# despertador.net
KiCad netlist of a schematic drawn in EAGLE
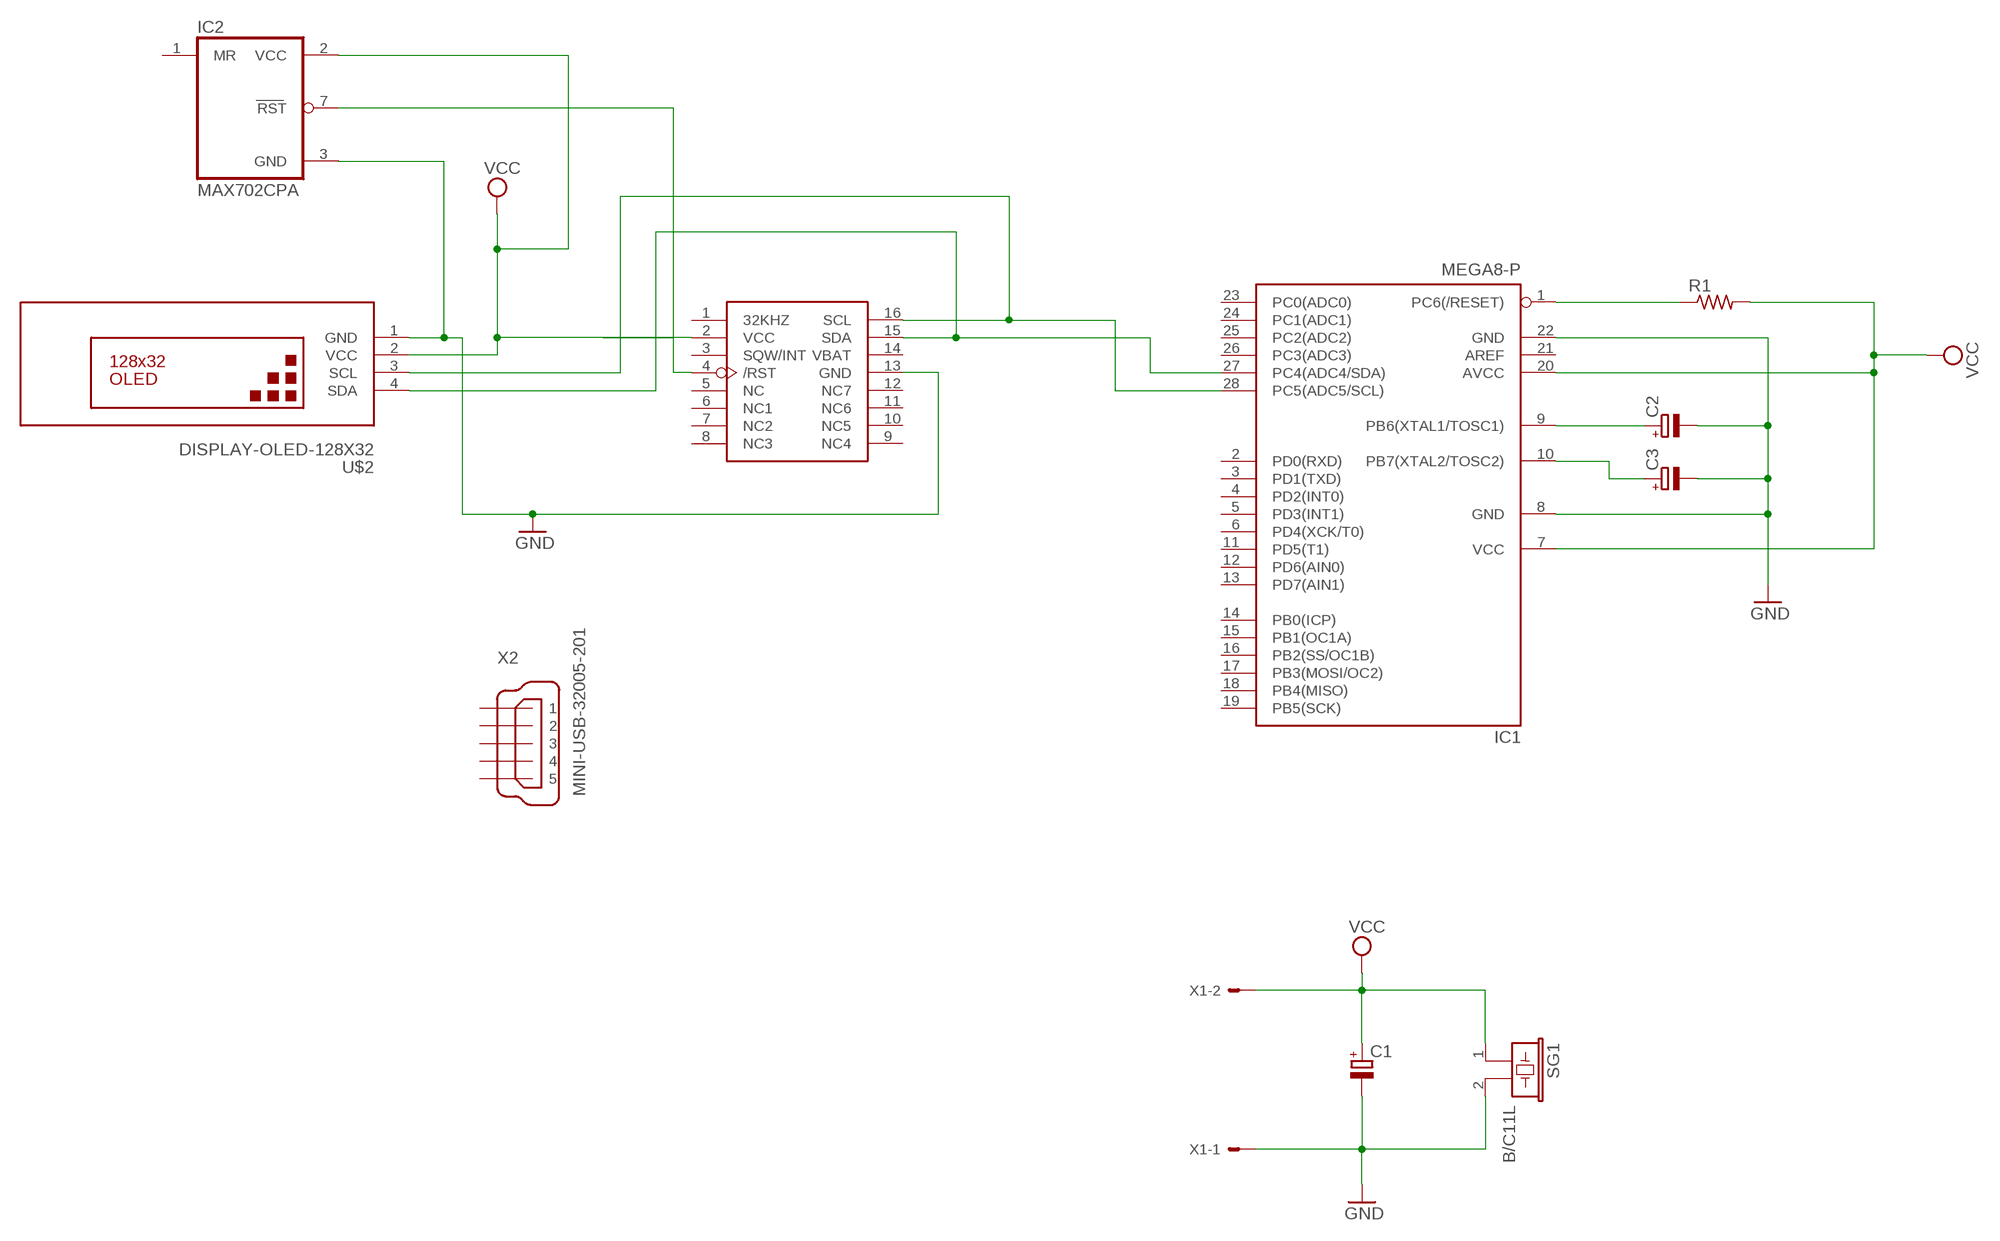
[diagram p0: schematic, sheet 1]

(export (version "E")
  (design (tool "Eeschema 10.0.6"))
  (components
    (comp (ref "C1")
      (value "CPOL-EUE2.5-6")
      (footprint "eagle-import:E2,5-6")
      (libsource (lib "eagle-import") (part "CPOL-EUE2.5-6"))
    )
    (comp (ref "C2")
      (value "CPOL-EUE2.5-6")
      (footprint "eagle-import:E2,5-6")
      (libsource (lib "eagle-import") (part "CPOL-EUE2.5-6"))
    )
    (comp (ref "C3")
      (value "CPOL-EUE2.5-6")
      (footprint "eagle-import:E2,5-6")
      (libsource (lib "eagle-import") (part "CPOL-EUE2.5-6"))
    )
    (comp (ref "IC1")
      (value "MEGA8-P")
      (footprint "eagle-import:DIL28-3")
      (libsource (lib "eagle-import") (part "MEGA8-P"))
    )
    (comp (ref "IC2")
      (value "MAX702CPA")
      (footprint "eagle-import:DIL08")
      (fields (field (name "MF") "MAXIM") (field (name "MPN") "MAX702CPA+"))
      (libsource (lib "eagle-import") (part "MAX702CPA"))
    )
    (comp (ref "R1")
      (value "R-US_0207/10")
      (footprint "eagle-import:0207_10")
      (libsource (lib "eagle-import") (part "R-US_0207/10"))
    )
    (comp (ref "SG1")
      (value "B/C11L")
      (footprint "eagle-import:B_C11L")
      (libsource (lib "eagle-import") (part "B/C11L"))
    )
    (comp (ref "U$2")
      (value "DISPLAY-OLED-128X32")
      (footprint "eagle-import:DISPLAY-OLED-128X32")
      (libsource (lib "eagle-import") (part "DISPLAY-OLED-128X32"))
    )
    (comp (ref "U$3")
      (value "DS3231")
      (footprint "eagle-import:PDIP")
      (libsource (lib "eagle-import") (part "DS3231"))
    )
    (comp (ref "X1")
      (value "KK-156-2")
      (footprint "eagle-import:KK-156-2")
      (fields (field (name "MF") "MOLEX"))
      (libsource (lib "eagle-import") (part "KK-156-2"))
    )
    (comp (ref "X2")
      (value "MINI-USB-32005-201")
      (footprint "eagle-import:32005-201")
      (libsource (lib "eagle-import") (part "MINI-USB-32005-201"))
    )
  )
  (nets
    (net (code "1") (name "GND") (class "Default")
      (node (ref "C1") (pin "-") (pinfunction "-_-") (pintype "passive"))
      (node (ref "C2") (pin "-") (pinfunction "-_-") (pintype "passive"))
      (node (ref "C3") (pin "-") (pinfunction "-_-") (pintype "passive"))
      (node (ref "IC1") (pin "22") (pinfunction "GND_22") (pintype "power_in"))
      (node (ref "IC1") (pin "8") (pinfunction "GND_8") (pintype "power_in"))
      (node (ref "IC2") (pin "3") (pinfunction "GND_3") (pintype "power_in"))
      (node (ref "SG1") (pin "2") (pinfunction "2_2") (pintype "passive"))
      (node (ref "U$2") (pin "1") (pinfunction "GND_1") (pintype "power_in"))
      (node (ref "U$3") (pin "13") (pinfunction "GND_13") (pintype "power_in"))
      (node (ref "X1") (pin "1") (pinfunction "S_1") (pintype "passive"))
    )
    (net (code "2") (name "Net-(IC1-PB6(XTAL1{slash}TOSC1))") (class "Default")
      (node (ref "C2") (pin "+") (pinfunction "+_+") (pintype "passive"))
      (node (ref "IC1") (pin "9") (pinfunction "PB6(XTAL1/TOSC1)_9") (pintype "bidirectional"))
    )
    (net (code "3") (name "Net-(IC1-PB7(XTAL2{slash}TOSC2))") (class "Default")
      (node (ref "C3") (pin "+") (pinfunction "+_+") (pintype "passive"))
      (node (ref "IC1") (pin "10") (pinfunction "PB7(XTAL2/TOSC2)_10") (pintype "bidirectional"))
    )
    (net (code "4") (name "Net-(IC1-PC4(ADC4{slash}SDA))") (class "Default")
      (node (ref "IC1") (pin "27") (pinfunction "PC4(ADC4/SDA)_27") (pintype "bidirectional"))
      (node (ref "U$2") (pin "4") (pinfunction "SDA_4") (pintype "bidirectional"))
      (node (ref "U$3") (pin "15") (pinfunction "SDA_15") (pintype "bidirectional"))
    )
    (net (code "5") (name "Net-(IC1-PC5(ADC5{slash}SCL))") (class "Default")
      (node (ref "IC1") (pin "28") (pinfunction "PC5(ADC5/SCL)_28") (pintype "bidirectional"))
      (node (ref "U$2") (pin "3") (pinfunction "SCL_3") (pintype "bidirectional"))
      (node (ref "U$3") (pin "16") (pinfunction "SCL_16") (pintype "bidirectional"))
    )
    (net (code "6") (name "Net-(IC1-PC6({slash}RESET))") (class "Default")
      (node (ref "IC1") (pin "1") (pinfunction "PC6(/RESET)_1") (pintype "bidirectional"))
      (node (ref "R1") (pin "1") (pinfunction "1_1") (pintype "passive"))
    )
    (net (code "7") (name "Net-(IC2-RST)") (class "Default")
      (node (ref "IC2") (pin "7") (pinfunction "RST_7") (pintype "output"))
      (node (ref "U$3") (pin "4") (pinfunction "/RST_4") (pintype "bidirectional"))
    )
    (net (code "8") (name "VCC") (class "Default")
      (node (ref "C1") (pin "+") (pinfunction "+_+") (pintype "passive"))
      (node (ref "IC1") (pin "20") (pinfunction "AVCC_20") (pintype "power_in"))
      (node (ref "IC1") (pin "7") (pinfunction "VCC_7") (pintype "power_in"))
      (node (ref "IC2") (pin "2") (pinfunction "VCC_2") (pintype "power_in"))
      (node (ref "R1") (pin "2") (pinfunction "2_2") (pintype "passive"))
      (node (ref "SG1") (pin "1") (pinfunction "1_1") (pintype "passive"))
      (node (ref "U$2") (pin "2") (pinfunction "VCC_2") (pintype "power_in"))
      (node (ref "U$3") (pin "2") (pinfunction "VCC_2") (pintype "power_in"))
      (node (ref "X1") (pin "2") (pinfunction "S_2") (pintype "passive"))
    )
    (net (code "9") (name "unconnected-(IC1-AREF-Pad21)") (class "Default")
      (node (ref "IC1") (pin "21") (pinfunction "AREF_21") (pintype "passive"))
    )
    (net (code "10") (name "unconnected-(IC1-PB0(ICP)-Pad14)") (class "Default")
      (node (ref "IC1") (pin "14") (pinfunction "PB0(ICP)_14") (pintype "bidirectional"))
    )
    (net (code "11") (name "unconnected-(IC1-PB1(OC1A)-Pad15)") (class "Default")
      (node (ref "IC1") (pin "15") (pinfunction "PB1(OC1A)_15") (pintype "bidirectional"))
    )
    (net (code "12") (name "unconnected-(IC1-PB2(SS{slash}OC1B)-Pad16)") (class "Default")
      (node (ref "IC1") (pin "16") (pinfunction "PB2(SS/OC1B)_16") (pintype "bidirectional"))
    )
    (net (code "13") (name "unconnected-(IC1-PB3(MOSI{slash}OC2)-Pad17)") (class "Default")
      (node (ref "IC1") (pin "17") (pinfunction "PB3(MOSI/OC2)_17") (pintype "bidirectional"))
    )
    (net (code "14") (name "unconnected-(IC1-PB4(MISO)-Pad18)") (class "Default")
      (node (ref "IC1") (pin "18") (pinfunction "PB4(MISO)_18") (pintype "bidirectional"))
    )
    (net (code "15") (name "unconnected-(IC1-PB5(SCK)-Pad19)") (class "Default")
      (node (ref "IC1") (pin "19") (pinfunction "PB5(SCK)_19") (pintype "bidirectional"))
    )
    (net (code "16") (name "unconnected-(IC1-PC0(ADC0)-Pad23)") (class "Default")
      (node (ref "IC1") (pin "23") (pinfunction "PC0(ADC0)_23") (pintype "bidirectional"))
    )
    (net (code "17") (name "unconnected-(IC1-PC1(ADC1)-Pad24)") (class "Default")
      (node (ref "IC1") (pin "24") (pinfunction "PC1(ADC1)_24") (pintype "bidirectional"))
    )
    (net (code "18") (name "unconnected-(IC1-PC2(ADC2)-Pad25)") (class "Default")
      (node (ref "IC1") (pin "25") (pinfunction "PC2(ADC2)_25") (pintype "bidirectional"))
    )
    (net (code "19") (name "unconnected-(IC1-PC3(ADC3)-Pad26)") (class "Default")
      (node (ref "IC1") (pin "26") (pinfunction "PC3(ADC3)_26") (pintype "bidirectional"))
    )
    (net (code "20") (name "unconnected-(IC1-PD0(RXD)-Pad2)") (class "Default")
      (node (ref "IC1") (pin "2") (pinfunction "PD0(RXD)_2") (pintype "bidirectional"))
    )
    (net (code "21") (name "unconnected-(IC1-PD1(TXD)-Pad3)") (class "Default")
      (node (ref "IC1") (pin "3") (pinfunction "PD1(TXD)_3") (pintype "bidirectional"))
    )
    (net (code "22") (name "unconnected-(IC1-PD2(INT0)-Pad4)") (class "Default")
      (node (ref "IC1") (pin "4") (pinfunction "PD2(INT0)_4") (pintype "bidirectional"))
    )
    (net (code "23") (name "unconnected-(IC1-PD3(INT1)-Pad5)") (class "Default")
      (node (ref "IC1") (pin "5") (pinfunction "PD3(INT1)_5") (pintype "bidirectional"))
    )
    (net (code "24") (name "unconnected-(IC1-PD4(XCK{slash}T0)-Pad6)") (class "Default")
      (node (ref "IC1") (pin "6") (pinfunction "PD4(XCK/T0)_6") (pintype "bidirectional"))
    )
    (net (code "25") (name "unconnected-(IC1-PD5(T1)-Pad11)") (class "Default")
      (node (ref "IC1") (pin "11") (pinfunction "PD5(T1)_11") (pintype "bidirectional"))
    )
    (net (code "26") (name "unconnected-(IC1-PD6(AIN0)-Pad12)") (class "Default")
      (node (ref "IC1") (pin "12") (pinfunction "PD6(AIN0)_12") (pintype "bidirectional"))
    )
    (net (code "27") (name "unconnected-(IC1-PD7(AIN1)-Pad13)") (class "Default")
      (node (ref "IC1") (pin "13") (pinfunction "PD7(AIN1)_13") (pintype "bidirectional"))
    )
    (net (code "28") (name "unconnected-(IC2-MR-Pad1)") (class "Default")
      (node (ref "IC2") (pin "1") (pinfunction "MR_1") (pintype "input"))
    )
    (net (code "29") (name "unconnected-(U$3-32KHZ-Pad1)") (class "Default")
      (node (ref "U$3") (pin "1") (pinfunction "32KHZ_1") (pintype "bidirectional"))
    )
    (net (code "30") (name "unconnected-(U$3-NC-Pad5)") (class "Default")
      (node (ref "U$3") (pin "5") (pinfunction "NC_5") (pintype "bidirectional"))
    )
    (net (code "31") (name "unconnected-(U$3-NC1-Pad6)") (class "Default")
      (node (ref "U$3") (pin "6") (pinfunction "NC1_6") (pintype "bidirectional"))
    )
    (net (code "32") (name "unconnected-(U$3-NC2-Pad7)") (class "Default")
      (node (ref "U$3") (pin "7") (pinfunction "NC2_7") (pintype "bidirectional"))
    )
    (net (code "33") (name "unconnected-(U$3-NC3-Pad8)") (class "Default")
      (node (ref "U$3") (pin "8") (pinfunction "NC3_8") (pintype "bidirectional"))
    )
    (net (code "34") (name "unconnected-(U$3-NC4-Pad9)") (class "Default")
      (node (ref "U$3") (pin "9") (pinfunction "NC4_9") (pintype "bidirectional"))
    )
    (net (code "35") (name "unconnected-(U$3-NC5-Pad10)") (class "Default")
      (node (ref "U$3") (pin "10") (pinfunction "NC5_10") (pintype "bidirectional"))
    )
    (net (code "36") (name "unconnected-(U$3-NC6-Pad11)") (class "Default")
      (node (ref "U$3") (pin "11") (pinfunction "NC6_11") (pintype "bidirectional"))
    )
    (net (code "37") (name "unconnected-(U$3-NC7-Pad12)") (class "Default")
      (node (ref "U$3") (pin "12") (pinfunction "NC7_12") (pintype "bidirectional"))
    )
    (net (code "38") (name "unconnected-(U$3-SQW{slash}INT-Pad3)") (class "Default")
      (node (ref "U$3") (pin "3") (pinfunction "SQW/INT_3") (pintype "bidirectional"))
    )
    (net (code "39") (name "unconnected-(U$3-VBAT-Pad14)") (class "Default")
      (node (ref "U$3") (pin "14") (pinfunction "VBAT_14") (pintype "bidirectional"))
    )
    (net (code "40") (name "unconnected-(X2-Pad1)") (class "Default")
      (node (ref "X2") (pin "1") (pinfunction "1_1") (pintype "passive"))
    )
    (net (code "41") (name "unconnected-(X2-Pad2)") (class "Default")
      (node (ref "X2") (pin "2") (pinfunction "2_2") (pintype "passive"))
    )
    (net (code "42") (name "unconnected-(X2-Pad3)") (class "Default")
      (node (ref "X2") (pin "3") (pinfunction "3_3") (pintype "passive"))
    )
    (net (code "43") (name "unconnected-(X2-Pad4)") (class "Default")
      (node (ref "X2") (pin "4") (pinfunction "4_4") (pintype "passive"))
    )
    (net (code "44") (name "unconnected-(X2-Pad5)") (class "Default")
      (node (ref "X2") (pin "5") (pinfunction "5_5") (pintype "passive"))
    )
  )
)
